# Audio_Amplifier_3W_PAM8403_Schematics_La.net
KiCad netlist of a schematic drawn in Altium Designer
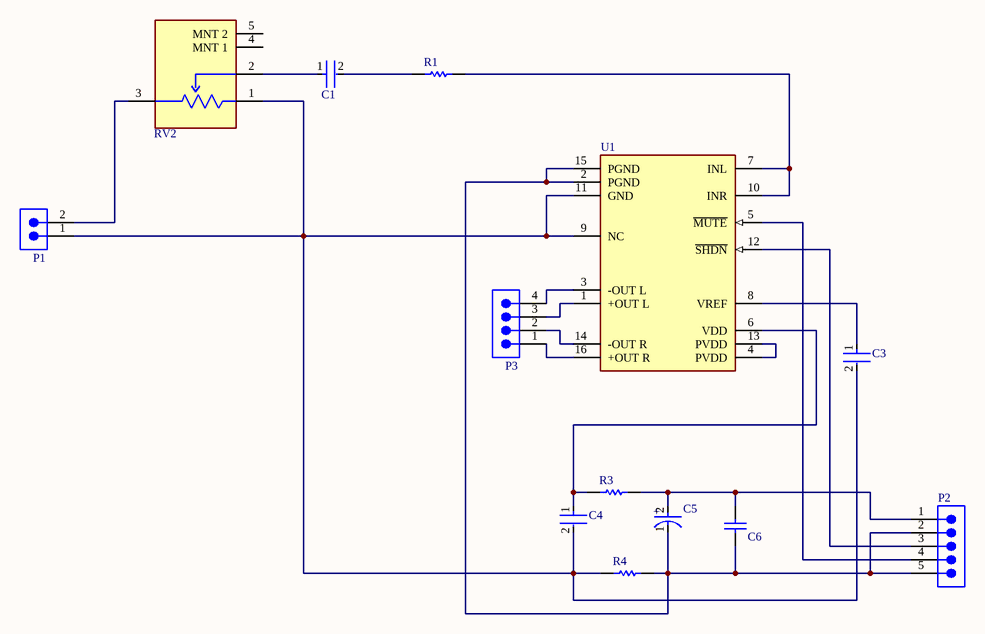
[diagram p0: Audio Amplifier 3W PAM8403 Schematics Layout.SchDoc]

(export (version "E")
  (design (tool "Eeschema 10.0.6"))
  (components
    (comp (ref "C1")
      (value "LMK063BC6474MPLF")
      (footprint "FP-0201-L_0_6_0_09-W_0_3-MFG")
      (description "0.47 µF ±20% 10V Ceramic Capacitor X6S 0201 (0603 Metric)")
      (libsource (lib "Altium Content Vault") (part "b4654b650e69147ec39a6b967a45e02"))
    )
    (comp (ref "C3")
      (value "GCD21BR72A104MA01L")
      (footprint "FP-GCD21B-0_15-MFG")
      (description "Chip Multilayer Ceramic Capacitors for Automotive, 0805, 0.10uF, X7R, 15%, 20%, 100V, Grade 1")
      (libsource (lib "Altium Content Vault") (part "b4654b650e69147ec39a6b967a45e02"))
    )
    (comp (ref "C4")
      (value "GRM188R61A106ME69J")
      (footprint "FP-GRM188-0_15-IPC_C")
      (description "Chip Multilayer Ceramic Capacitors for General Purpose, 0603, 10uF, X5R, 15%, 20%, 10V")
      (fields (field (name "TOLERANCE") "20%"))
      (libsource (lib "Altium Content Vault") (part "02cd4be3c70576c341d710602a673aa"))
    )
    (comp (ref "C5")
      (value "EEUFM1E101B")
      (footprint "FP-RAD-TH-D_6_3_0_5-L_11-MFG")
      (description "Aluminum Electrolytic Capacitors (Radial Lead Type) 100uF ±20% 25V")
      (fields (field (name "TOLERANCE") "20%"))
      (libsource (lib "Altium Content Vault") (part "a00bbbee19879c290e62620ae7e47b1"))
    )
    (comp (ref "C6")
      (value "0805YD105MAT2A")
      (footprint "CAPC2013X140X50NL20T25")
      (description "1 µF ±20% 16V Ceramic Capacitor X5R 0805 (2012 Metric)")
      (fields (field (name "MANUFACTURER") "AVX Interconnect / Elco"))
      (libsource (lib "Altium Content Vault") (part "CAP"))
    )
    (comp (ref "P1")
      (value "61300211121")
      (footprint "61300211121")
      (description "THT Vertical Pin Header WR-PHD, Pitch 2.54 mm, Single Row, 2 pins")
      (libsource (lib "Altium Content Vault") (part "Header_Male_1R_02P"))
    )
    (comp (ref "P2")
      (value "61300511121")
      (footprint "61300511121")
      (description "THT Vertical Pin Header WR-PHD, Pitch 2.54 mm, Single Row, 5 pins")
      (libsource (lib "Altium Content Vault") (part "Header_Male_1R_05P"))
    )
    (comp (ref "P3")
      (value "61300411121")
      (footprint "61300411121")
      (description "THT Vertical Pin Header WR-PHD, Pitch 2.54 mm, Single Row, 4 pins")
      (libsource (lib "Altium Content Vault") (part "Header_Male_1R_04P"))
    )
    (comp (ref "R1")
      (value "20K 5% 1210(3225)")
      (footprint "RESC1210(3225)_M")
      (description "20K 0.5W 5% 1210 (3225 Metric)  SMD")
      (fields (field (name "POWER") "0.5 W") (field (name "TOLERANCE") "5 %"))
      (libsource (lib "Altium Content Vault") (part "RES"))
    )
    (comp (ref "R3")
      (value "RC1206FR-1010RL")
      (footprint "RESC3116X65X40LL10T20")
      (fields (field (name "MANUFACTURER") "Yageo"))
      (libsource (lib "Altium Content Vault") (part "RES"))
    )
    (comp (ref "R4")
      (value "SG73S1ETTP1R0J")
      (footprint "RESC1005X40X25LL10T10")
      (fields (field (name "MANUFACTURER") "KOA Speer"))
      (libsource (lib "Altium Content Vault") (part "RES"))
    )
    (comp (ref "RV2")
      (value "RK09L1140A2U")
      (footprint "FP-RK09L1140A2U-MFG")
      (description "9mm Size Metal Shaft Snap-in Type RK09L Series")
      (fields
        (field (name "TOLERANCE") "20%")
        (field (name "OCTOPART") "https://octopart.com/rk09l1140a2u-alps-7850070")
      )
      (libsource (lib "Altium Content Vault") (part "0c568a6e0ac31b8b52ae5f6704acd43"))
    )
    (comp (ref "U1")
      (value "PAM8403DR")
      (footprint "FP-SO-16-MFG")
      (description "IC AMP CLASS D STEREO 3W 16SOP")
      (fields
        (field (name "MANUFACTURER") "Diodes Inc.")
        (field (name "OCTOPART") "https://octopart.com/pam8403dr-diodes+inc.-29030487")
      )
      (libsource (lib "Altium Content Vault") (part "885d396dc31e3b4190d53cf5014fb37"))
    )
  )
  (nets
    (net (code "1") (name "Net-(C1-Pad1)") (class "Default")
      (node (ref "C1") (pin "1") (pinfunction "1_1") (pintype "passive"))
      (node (ref "RV2") (pin "2") (pinfunction "2_2") (pintype "passive"))
    )
    (net (code "2") (name "Net-(C1-Pad2)") (class "Default")
      (node (ref "C1") (pin "2") (pinfunction "2_2") (pintype "passive"))
      (node (ref "R1") (pin "1") (pinfunction "1_1") (pintype "passive"))
    )
    (net (code "3") (name "Net-(C5-A)") (class "Default")
      (node (ref "C5") (pin "2") (pinfunction "A_2") (pintype "passive"))
      (node (ref "C6") (pin "2") (pinfunction "2_2") (pintype "passive"))
      (node (ref "P2") (pin "1") (pinfunction "1_1") (pintype "passive"))
      (node (ref "R3") (pin "2") (pinfunction "2_2") (pintype "passive"))
    )
    (net (code "4") (name "Net-(C5-C)") (class "Default")
      (node (ref "C5") (pin "1") (pinfunction "C_1") (pintype "passive"))
      (node (ref "C6") (pin "1") (pinfunction "1_1") (pintype "passive"))
      (node (ref "P2") (pin "2") (pinfunction "2_2") (pintype "passive"))
      (node (ref "P2") (pin "5") (pinfunction "5_5") (pintype "passive"))
      (node (ref "R4") (pin "2") (pinfunction "2_2") (pintype "passive"))
      (node (ref "U1") (pin "15") (pinfunction "PGND_15") (pintype "power_in"))
      (node (ref "U1") (pin "2") (pinfunction "PGND_2") (pintype "power_in"))
    )
    (net (code "5") (name "Net-(P1-Pad2)") (class "Default")
      (node (ref "P1") (pin "2") (pinfunction "2_2") (pintype "passive"))
      (node (ref "RV2") (pin "3") (pinfunction "3_3") (pintype "passive"))
    )
    (net (code "6") (name "Net-(U1-+OUT_L)") (class "Default")
      (node (ref "P3") (pin "3") (pinfunction "3_3") (pintype "passive"))
      (node (ref "U1") (pin "1") (pinfunction "+OUT_L_1") (pintype "passive"))
    )
    (net (code "7") (name "Net-(U1-+OUT_R)") (class "Default")
      (node (ref "P3") (pin "1") (pinfunction "1_1") (pintype "passive"))
      (node (ref "U1") (pin "16") (pinfunction "+OUT_R_16") (pintype "passive"))
    )
    (net (code "8") (name "Net-(U1--OUT_L)") (class "Default")
      (node (ref "P3") (pin "4") (pinfunction "4_4") (pintype "passive"))
      (node (ref "U1") (pin "3") (pinfunction "-OUT_L_3") (pintype "passive"))
    )
    (net (code "9") (name "Net-(U1--OUT_R)") (class "Default")
      (node (ref "P3") (pin "2") (pinfunction "2_2") (pintype "passive"))
      (node (ref "U1") (pin "14") (pinfunction "-OUT_R_14") (pintype "passive"))
    )
    (net (code "10") (name "Net-(U1-GND)") (class "Default")
      (node (ref "C3") (pin "2") (pinfunction "2_2") (pintype "passive"))
      (node (ref "C4") (pin "2") (pinfunction "2_2") (pintype "passive"))
      (node (ref "P1") (pin "1") (pinfunction "1_1") (pintype "passive"))
      (node (ref "R4") (pin "1") (pinfunction "1_1") (pintype "passive"))
      (node (ref "RV2") (pin "1") (pinfunction "1_1") (pintype "passive"))
      (node (ref "U1") (pin "11") (pinfunction "GND_11") (pintype "power_in"))
      (node (ref "U1") (pin "9") (pinfunction "NC_9") (pintype "passive"))
    )
    (net (code "11") (name "Net-(U1-INL)") (class "Default")
      (node (ref "R1") (pin "2") (pinfunction "2_2") (pintype "passive"))
      (node (ref "U1") (pin "10") (pinfunction "INR_10") (pintype "passive"))
      (node (ref "U1") (pin "7") (pinfunction "INL_7") (pintype "passive"))
    )
    (net (code "12") (name "Net-(U1-PVDD-Pad13)") (class "Default")
      (node (ref "U1") (pin "13") (pinfunction "PVDD_13") (pintype "power_in"))
      (node (ref "U1") (pin "4") (pinfunction "PVDD_4") (pintype "power_in"))
    )
    (net (code "13") (name "Net-(U1-VDD)") (class "Default")
      (node (ref "C4") (pin "1") (pinfunction "1_1") (pintype "passive"))
      (node (ref "R3") (pin "1") (pinfunction "1_1") (pintype "passive"))
      (node (ref "U1") (pin "6") (pinfunction "VDD_6") (pintype "power_in"))
    )
    (net (code "14") (name "Net-(U1-VREF)") (class "Default")
      (node (ref "C3") (pin "1") (pinfunction "1_1") (pintype "passive"))
      (node (ref "U1") (pin "8") (pinfunction "VREF_8") (pintype "passive"))
    )
    (net (code "15") (name "Net-(U1-~{MUTE})") (class "Default")
      (node (ref "P2") (pin "4") (pinfunction "4_4") (pintype "passive"))
      (node (ref "U1") (pin "5") (pinfunction "~{MUTE}_5") (pintype "input"))
    )
    (net (code "16") (name "Net-(U1-~{SHDN})") (class "Default")
      (node (ref "P2") (pin "3") (pinfunction "3_3") (pintype "passive"))
      (node (ref "U1") (pin "12") (pinfunction "~{SHDN}_12") (pintype "input"))
    )
    (net (code "17") (name "unconnected-(RV2-MNT_1-Pad4)") (class "Default")
      (node (ref "RV2") (pin "4") (pinfunction "MNT_1_4") (pintype "passive"))
    )
    (net (code "18") (name "unconnected-(RV2-MNT_2-Pad5)") (class "Default")
      (node (ref "RV2") (pin "5") (pinfunction "MNT_2_5") (pintype "passive"))
    )
  )
)
